# Access_System_ADP.net
KiCad netlist of a schematic drawn in Altium Designer
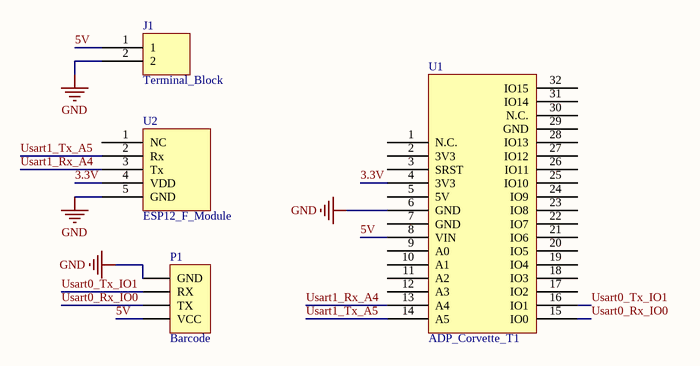
[diagram p0: Access_System_ADP.SchDoc]

(export (version "E")
  (design (tool "Eeschema 10.0.6"))
  (components
    (comp (ref "J1")
      (value "Terminal_Block")
      (footprint "terminal block")
      (libsource (lib "Lab_share") (part "Terminal Block"))
    )
    (comp (ref "P1")
      (value "Barcode")
      (footprint "HDR1X4")
      (description "Header, 4-Pin")
      (fields (field (name "PUBLISHER") "Altium Limited"))
      (libsource (lib "Miscellaneous Connectors") (part "Header 4"))
    )
    (comp (ref "U1")
      (value "ADP_Corvette_T1")
      (footprint "Corvette_T1")
      (libsource (lib "Lab_share") (part "Corvette_T1"))
    )
    (comp (ref "U2")
      (value "ESP12_F_Module")
      (footprint "ESP12_F_Holtek")
      (libsource (lib "Lab_share") (part "ESP12_F_Holtek"))
    )
  )
  (nets
    (net (code "1") (name "/3.3V") (class "Default")
      (node (ref "U1") (pin "4") (pinfunction "3V3_4") (pintype "passive"))
      (node (ref "U2") (pin "4") (pinfunction "VDD_4") (pintype "passive"))
    )
    (net (code "2") (name "/5V") (class "Default")
      (node (ref "J1") (pin "1") (pinfunction "1_1") (pintype "passive"))
      (node (ref "P1") (pin "4") (pinfunction "VCC_4") (pintype "passive"))
      (node (ref "U1") (pin "8") (pinfunction "VIN_8") (pintype "passive"))
    )
    (net (code "3") (name "/Usart0_Rx_IO0") (class "Default")
      (node (ref "P1") (pin "3") (pinfunction "TX_3") (pintype "passive"))
      (node (ref "U1") (pin "15") (pinfunction "IO0_15") (pintype "passive"))
    )
    (net (code "4") (name "/Usart0_Tx_IO1") (class "Default")
      (node (ref "P1") (pin "2") (pinfunction "RX_2") (pintype "passive"))
      (node (ref "U1") (pin "16") (pinfunction "IO1_16") (pintype "passive"))
    )
    (net (code "5") (name "/Usart1_Rx_A4") (class "Default")
      (node (ref "U1") (pin "13") (pinfunction "A4_13") (pintype "passive"))
      (node (ref "U2") (pin "3") (pinfunction "Tx_3") (pintype "passive"))
    )
    (net (code "6") (name "/Usart1_Tx_A5") (class "Default")
      (node (ref "U1") (pin "14") (pinfunction "A5_14") (pintype "passive"))
      (node (ref "U2") (pin "2") (pinfunction "Rx_2") (pintype "passive"))
    )
    (net (code "7") (name "GND") (class "Default")
      (node (ref "J1") (pin "2") (pinfunction "2_2") (pintype "passive"))
      (node (ref "P1") (pin "1") (pinfunction "GND_1") (pintype "passive"))
      (node (ref "U1") (pin "6") (pinfunction "GND_6") (pintype "passive"))
      (node (ref "U2") (pin "5") (pinfunction "GND_5") (pintype "passive"))
    )
    (net (code "8") (name "unconnected-(U1-3V3-Pad2)") (class "Default")
      (node (ref "U1") (pin "2") (pinfunction "3V3_2") (pintype "passive"))
    )
    (net (code "9") (name "unconnected-(U1-5V-Pad5)") (class "Default")
      (node (ref "U1") (pin "5") (pinfunction "5V_5") (pintype "passive"))
    )
    (net (code "10") (name "unconnected-(U1-A0-Pad9)") (class "Default")
      (node (ref "U1") (pin "9") (pinfunction "A0_9") (pintype "passive"))
    )
    (net (code "11") (name "unconnected-(U1-A1-Pad10)") (class "Default")
      (node (ref "U1") (pin "10") (pinfunction "A1_10") (pintype "passive"))
    )
    (net (code "12") (name "unconnected-(U1-A2-Pad11)") (class "Default")
      (node (ref "U1") (pin "11") (pinfunction "A2_11") (pintype "passive"))
    )
    (net (code "13") (name "unconnected-(U1-A3-Pad12)") (class "Default")
      (node (ref "U1") (pin "12") (pinfunction "A3_12") (pintype "passive"))
    )
    (net (code "14") (name "unconnected-(U1-GND-Pad7)") (class "Default")
      (node (ref "U1") (pin "7") (pinfunction "GND_7") (pintype "passive"))
    )
    (net (code "15") (name "unconnected-(U1-GND-Pad29)") (class "Default")
      (node (ref "U1") (pin "29") (pinfunction "GND_29") (pintype "passive"))
    )
    (net (code "16") (name "unconnected-(U1-IO2-Pad17)") (class "Default")
      (node (ref "U1") (pin "17") (pinfunction "IO2_17") (pintype "passive"))
    )
    (net (code "17") (name "unconnected-(U1-IO3-Pad18)") (class "Default")
      (node (ref "U1") (pin "18") (pinfunction "IO3_18") (pintype "passive"))
    )
    (net (code "18") (name "unconnected-(U1-IO4-Pad19)") (class "Default")
      (node (ref "U1") (pin "19") (pinfunction "IO4_19") (pintype "passive"))
    )
    (net (code "19") (name "unconnected-(U1-IO5-Pad20)") (class "Default")
      (node (ref "U1") (pin "20") (pinfunction "IO5_20") (pintype "passive"))
    )
    (net (code "20") (name "unconnected-(U1-IO6-Pad21)") (class "Default")
      (node (ref "U1") (pin "21") (pinfunction "IO6_21") (pintype "passive"))
    )
    (net (code "21") (name "unconnected-(U1-IO7-Pad22)") (class "Default")
      (node (ref "U1") (pin "22") (pinfunction "IO7_22") (pintype "passive"))
    )
    (net (code "22") (name "unconnected-(U1-IO8-Pad23)") (class "Default")
      (node (ref "U1") (pin "23") (pinfunction "IO8_23") (pintype "passive"))
    )
    (net (code "23") (name "unconnected-(U1-IO9-Pad24)") (class "Default")
      (node (ref "U1") (pin "24") (pinfunction "IO9_24") (pintype "passive"))
    )
    (net (code "24") (name "unconnected-(U1-IO10-Pad25)") (class "Default")
      (node (ref "U1") (pin "25") (pinfunction "IO10_25") (pintype "passive"))
    )
    (net (code "25") (name "unconnected-(U1-IO11-Pad26)") (class "Default")
      (node (ref "U1") (pin "26") (pinfunction "IO11_26") (pintype "passive"))
    )
    (net (code "26") (name "unconnected-(U1-IO12-Pad27)") (class "Default")
      (node (ref "U1") (pin "27") (pinfunction "IO12_27") (pintype "passive"))
    )
    (net (code "27") (name "unconnected-(U1-IO13-Pad28)") (class "Default")
      (node (ref "U1") (pin "28") (pinfunction "IO13_28") (pintype "passive"))
    )
    (net (code "28") (name "unconnected-(U1-IO14-Pad31)") (class "Default")
      (node (ref "U1") (pin "31") (pinfunction "IO14_31") (pintype "passive"))
    )
    (net (code "29") (name "unconnected-(U1-IO15-Pad32)") (class "Default")
      (node (ref "U1") (pin "32") (pinfunction "IO15_32") (pintype "passive"))
    )
    (net (code "30") (name "unconnected-(U1-N.C.-Pad1)") (class "Default")
      (node (ref "U1") (pin "1") (pinfunction "N.C._1") (pintype "passive"))
    )
    (net (code "31") (name "unconnected-(U1-N.C.-Pad30)") (class "Default")
      (node (ref "U1") (pin "30") (pinfunction "N.C._30") (pintype "passive"))
    )
    (net (code "32") (name "unconnected-(U1-SRST-Pad3)") (class "Default")
      (node (ref "U1") (pin "3") (pinfunction "SRST_3") (pintype "passive"))
    )
    (net (code "33") (name "unconnected-(U2-NC-Pad1)") (class "Default")
      (node (ref "U2") (pin "1") (pinfunction "NC_1") (pintype "passive"))
    )
  )
)
